# Main.net
KiCad netlist of a schematic drawn in Altium Designer
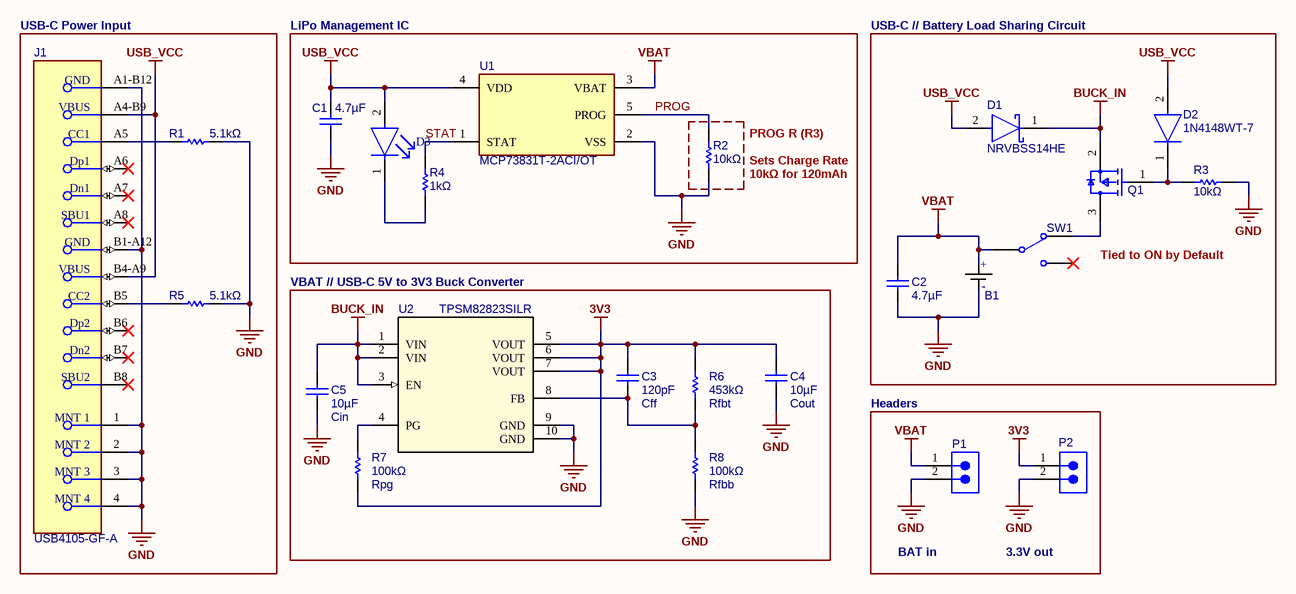
[diagram p0: Main.SchDoc]

(export (version "E")
  (design (tool "Eeschema 10.0.6"))
  (components
    (comp (ref "B1") (value "LiPo") (libsource (lib "LiPoSchematicLibrary") (part "3.7V 30mAh LiPo")))
    (comp (ref "C1")
      (value "4.7µF")
      (footprint "WCAP-CSGP_0603_L1.6W0.8H0.8_Reflow")
      (libsource (lib "Altium Content Vault") (part "Capacitor_Non-Polarized"))
    )
    (comp (ref "C2")
      (value "4.7µF")
      (footprint "WCAP-CSGP_0603_L1.6W0.8H0.8_Reflow")
      (libsource (lib "Altium Content Vault") (part "Capacitor_Non-Polarized"))
    )
    (comp (ref "C3")
      (value "120pF")
      (footprint "WCAP-CSGP_0603_L1.6W0.8H0.8_Reflow")
      (libsource (lib "Altium Content Vault") (part "Capacitor_Non-Polarized"))
    )
    (comp (ref "C4")
      (value "10µF")
      (footprint "WCAP-CSGP_0603_L1.6W0.8H0.8_Reflow")
      (description "10V tolerance")
      (libsource (lib "Altium Content Vault") (part "Capacitor_Non-Polarized"))
    )
    (comp (ref "C5")
      (value "10µF")
      (footprint "WCAP-CSGP_0603_L1.6W0.8H0.8_Reflow")
      (libsource (lib "Altium Content Vault") (part "Capacitor_Non-Polarized"))
    )
    (comp (ref "D1")
      (value "NRVBSS14HE")
      (footprint "FP-477AD-MFG")
      (description "NRVBSS14HE Rectifier Diode, Schottky, 1 Phase, 1 Element, 1A, 40V V(RRM), Silicon")
      (libsource (lib "Altium Content Vault") (part "c1678fac7984e62e0809fbf79c06691"))
    )
    (comp (ref "D2")
      (value "1N4148WT-7")
      (footprint "FP-SOD523-MFG")
      (description "DIODE GEN PURP 80V 125MA SOD523")
      (libsource (lib "Altium Content Vault") (part "d7152d700b627762746794eb795d46e"))
    )
    (comp (ref "D3")
      (value "LTST-C190KGKT")
      (footprint "FP-LTST-C190KGKT-MFG")
      (description "LED GREEN CLEAR CHIP SMD")
      (libsource (lib "Altium Content Vault") (part "8706943c75ba83719d021d2fdc84c58"))
    )
    (comp (ref "J1")
      (value "USB4105-GF-A")
      (footprint "FP-USB4105-GF-A-MFG")
      (description "CONN RCPT USB2.0 TYPEC 5A")
      (fields
        (field (name "MANUFACTURER") "GCT")
        (field (name "OCTOPART") "https://octopart.com/usb4105-gf-a-gct-106627878")
      )
      (libsource (lib "Altium Content Vault") (part "e7c17a616881a82b79941196b4bec10"))
    )
    (comp (ref "P1")
      (value "61300211121")
      (footprint "61300211121")
      (libsource (lib "Altium Content Vault") (part "Header_Male_1R_02P"))
    )
    (comp (ref "P2")
      (value "61300211121")
      (footprint "61300211121")
      (libsource (lib "Altium Content Vault") (part "Header_Male_1R_02P"))
    )
    (comp (ref "Q1")
      (value "IRLML6402TRPBF")
      (footprint "FP-Micro3-MFG")
      (description "MOSFET P-CH 20V 3.7A SOT-23")
      (fields
        (field (name "OCTOPART") "https://octopart.com/irlml6402trpbf-infineon-65874989")
        (field (name "MANUFACTURER") "Infineon")
      )
      (libsource (lib "Altium Content Vault") (part "566027c8dc92b5207d53ac25ab3eb60"))
    )
    (comp (ref "R1")
      (value "5.1kΩ")
      (footprint "RESC1608X55X25NL10T15")
      (libsource (lib "Altium Content Vault") (part "RES"))
    )
    (comp (ref "R2")
      (value "10kΩ")
      (footprint "RESC1608X55X25NL10T15")
      (libsource (lib "Altium Content Vault") (part "RES"))
    )
    (comp (ref "R3")
      (value "10kΩ")
      (footprint "RESC1608X55X25NL10T15")
      (libsource (lib "Altium Content Vault") (part "RES"))
    )
    (comp (ref "R4")
      (value "1kΩ")
      (footprint "RESC1608X55X25NL10T15")
      (libsource (lib "Altium Content Vault") (part "RES"))
    )
    (comp (ref "R5")
      (value "5.1kΩ")
      (footprint "RESC1608X55X25NL10T15")
      (libsource (lib "Altium Content Vault") (part "RES"))
    )
    (comp (ref "R6")
      (value "453kΩ")
      (footprint "RESC1608X55X25NL10T15")
      (libsource (lib "Altium Content Vault") (part "RES"))
    )
    (comp (ref "R7")
      (value "100kΩ")
      (footprint "RESC1608X55X25NL10T15")
      (libsource (lib "Altium Content Vault") (part "RES"))
    )
    (comp (ref "R8")
      (value "100kΩ")
      (footprint "RESC1608X55X25NL10T15")
      (libsource (lib "Altium Content Vault") (part "RES"))
    )
    (comp (ref "SW1")
      (value "450404015514")
      (footprint "450404015514")
      (description "450404015514 Slide Switch, 0.3A, 5Vdc, Smd Rohs Compliant: Yes")
      (libsource (lib "Altium Content Vault") (part "SPDT"))
    )
    (comp (ref "U1")
      (value "MCP73831T-2ACI/OT")
      (footprint "FP-C04-091-OT-IPC_B")
      (description "IC CONTROLLR LI-ION 4.2V SOT23-5")
      (libsource (lib "Altium Content Vault") (part "61f5a3bb3429d9e0caadea342aa3b19"))
    )
    (comp (ref "U2")
      (value "TPSM82823SILR")
      (footprint "SIL0010D-MFG")
      (description "No Description Available")
      (libsource (lib "TPSM82823SILR") (part "TPSM82823SILR"))
    )
  )
  (nets
    (net (code "1") (name "/PROG") (class "Default")
      (node (ref "R2") (pin "1") (pinfunction "1_1") (pintype "passive"))
      (node (ref "U1") (pin "5") (pinfunction "PROG_5") (pintype "passive"))
    )
    (net (code "2") (name "/STAT") (class "Default")
      (node (ref "R4") (pin "2") (pinfunction "2_2") (pintype "passive"))
      (node (ref "U1") (pin "1") (pinfunction "STAT_1") (pintype "passive"))
    )
    (net (code "3") (name "3V3") (class "Default")
      (node (ref "C3") (pin "2") (pinfunction "2_2") (pintype "passive"))
      (node (ref "C4") (pin "2") (pinfunction "2_2") (pintype "passive"))
      (node (ref "P2") (pin "1") (pinfunction "1_1") (pintype "passive"))
      (node (ref "R6") (pin "1") (pinfunction "1_1") (pintype "passive"))
      (node (ref "R7") (pin "2") (pinfunction "2_2") (pintype "passive"))
      (node (ref "U2") (pin "5") (pinfunction "VOUT_5") (pintype "power_in"))
      (node (ref "U2") (pin "6") (pinfunction "VOUT_6") (pintype "power_in"))
      (node (ref "U2") (pin "7") (pinfunction "VOUT_7") (pintype "power_in"))
    )
    (net (code "4") (name "BUCK_IN") (class "Default")
      (node (ref "C5") (pin "2") (pinfunction "2_2") (pintype "passive"))
      (node (ref "D1") (pin "1") (pinfunction "C_1") (pintype "passive"))
      (node (ref "Q1") (pin "2") (pinfunction "S_2") (pintype "passive"))
      (node (ref "U2") (pin "1") (pinfunction "VIN_1") (pintype "power_in"))
      (node (ref "U2") (pin "2") (pinfunction "VIN_2") (pintype "power_in"))
      (node (ref "U2") (pin "3") (pinfunction "EN_3") (pintype "input"))
    )
    (net (code "5") (name "GND") (class "Default")
      (node (ref "B1") (pin "1") (pinfunction "-_1") (pintype "passive"))
      (node (ref "C1") (pin "1") (pinfunction "1_1") (pintype "passive"))
      (node (ref "C2") (pin "1") (pinfunction "1_1") (pintype "passive"))
      (node (ref "C4") (pin "1") (pinfunction "1_1") (pintype "passive"))
      (node (ref "C5") (pin "1") (pinfunction "1_1") (pintype "passive"))
      (node (ref "J1") (pin "1") (pinfunction "MNT_1_1") (pintype "power_in"))
      (node (ref "J1") (pin "2") (pinfunction "MNT_2_2") (pintype "power_in"))
      (node (ref "J1") (pin "3") (pinfunction "MNT_3_3") (pintype "power_in"))
      (node (ref "J1") (pin "4") (pinfunction "MNT_4_4") (pintype "power_in"))
      (node (ref "J1") (pin "A1-B12") (pinfunction "GND_A1-B12") (pintype "power_in"))
      (node (ref "J1") (pin "B1-A12") (pinfunction "GND_B1-A12") (pintype "bidirectional"))
      (node (ref "P1") (pin "2") (pinfunction "2_2") (pintype "passive"))
      (node (ref "P2") (pin "2") (pinfunction "2_2") (pintype "passive"))
      (node (ref "R1") (pin "1") (pinfunction "1_1") (pintype "passive"))
      (node (ref "R2") (pin "2") (pinfunction "2_2") (pintype "passive"))
      (node (ref "R3") (pin "2") (pinfunction "2_2") (pintype "passive"))
      (node (ref "R5") (pin "1") (pinfunction "1_1") (pintype "passive"))
      (node (ref "R8") (pin "2") (pinfunction "2_2") (pintype "passive"))
      (node (ref "U1") (pin "2") (pinfunction "VSS_2") (pintype "power_in"))
      (node (ref "U2") (pin "10") (pinfunction "GND_10") (pintype "power_in"))
      (node (ref "U2") (pin "9") (pinfunction "GND_9") (pintype "power_in"))
    )
    (net (code "6") (name "Net-(D2-C)") (class "Default")
      (node (ref "D2") (pin "1") (pinfunction "C_1") (pintype "passive"))
      (node (ref "Q1") (pin "1") (pinfunction "G_1") (pintype "passive"))
      (node (ref "R3") (pin "1") (pinfunction "1_1") (pintype "passive"))
    )
    (net (code "7") (name "Net-(D3-C)") (class "Default")
      (node (ref "D3") (pin "1") (pinfunction "C_1") (pintype "passive"))
      (node (ref "R4") (pin "1") (pinfunction "1_1") (pintype "passive"))
    )
    (net (code "8") (name "Net-(J1-CC1)") (class "Default")
      (node (ref "J1") (pin "A5") (pinfunction "CC1_A5") (pintype "power_in"))
      (node (ref "R1") (pin "2") (pinfunction "2_2") (pintype "passive"))
    )
    (net (code "9") (name "Net-(J1-CC2)") (class "Default")
      (node (ref "J1") (pin "B5") (pinfunction "CC2_B5") (pintype "bidirectional"))
      (node (ref "R5") (pin "2") (pinfunction "2_2") (pintype "passive"))
    )
    (net (code "10") (name "Net-(Q1-D)") (class "Default")
      (node (ref "Q1") (pin "3") (pinfunction "D_3") (pintype "passive"))
      (node (ref "SW1") (pin "L1") (pinfunction "L1_L1") (pintype "passive"))
    )
    (net (code "11") (name "Net-(U2-FB)") (class "Default")
      (node (ref "C3") (pin "1") (pinfunction "1_1") (pintype "passive"))
      (node (ref "R6") (pin "2") (pinfunction "2_2") (pintype "passive"))
      (node (ref "R8") (pin "1") (pinfunction "1_1") (pintype "passive"))
      (node (ref "U2") (pin "8") (pinfunction "FB_8") (pintype "passive"))
    )
    (net (code "12") (name "Net-(U2-PG)") (class "Default")
      (node (ref "R7") (pin "1") (pinfunction "1_1") (pintype "passive"))
      (node (ref "U2") (pin "4") (pinfunction "PG_4") (pintype "open_collector"))
    )
    (net (code "13") (name "USB_VCC") (class "Default")
      (node (ref "C1") (pin "2") (pinfunction "2_2") (pintype "passive"))
      (node (ref "D1") (pin "2") (pinfunction "A_2") (pintype "passive"))
      (node (ref "D2") (pin "2") (pinfunction "A_2") (pintype "passive"))
      (node (ref "D3") (pin "2") (pinfunction "A_2") (pintype "passive"))
      (node (ref "J1") (pin "A4-B9") (pinfunction "VBUS_A4-B9") (pintype "power_in"))
      (node (ref "J1") (pin "B4-A9") (pinfunction "VBUS_B4-A9") (pintype "bidirectional"))
      (node (ref "U1") (pin "4") (pinfunction "VDD_4") (pintype "power_in"))
    )
    (net (code "14") (name "VBAT") (class "Default")
      (node (ref "B1") (pin "0") (pinfunction "+_0") (pintype "passive"))
      (node (ref "C2") (pin "2") (pinfunction "2_2") (pintype "passive"))
      (node (ref "P1") (pin "1") (pinfunction "1_1") (pintype "passive"))
      (node (ref "SW1") (pin "COM") (pinfunction "COM_COM") (pintype "passive"))
      (node (ref "U1") (pin "3") (pinfunction "VBAT_3") (pintype "power_in"))
    )
    (net (code "15") (name "unconnected-(J1-Dn1-PadA7)") (class "Default")
      (node (ref "J1") (pin "A7") (pinfunction "Dn1_A7") (pintype "bidirectional+no_connect"))
    )
    (net (code "16") (name "unconnected-(J1-Dn2-PadB7)") (class "Default")
      (node (ref "J1") (pin "B7") (pinfunction "Dn2_B7") (pintype "bidirectional+no_connect"))
    )
    (net (code "17") (name "unconnected-(J1-Dp1-PadA6)") (class "Default")
      (node (ref "J1") (pin "A6") (pinfunction "Dp1_A6") (pintype "bidirectional+no_connect"))
    )
    (net (code "18") (name "unconnected-(J1-Dp2-PadB6)") (class "Default")
      (node (ref "J1") (pin "B6") (pinfunction "Dp2_B6") (pintype "bidirectional+no_connect"))
    )
    (net (code "19") (name "unconnected-(J1-SBU1-PadA8)") (class "Default")
      (node (ref "J1") (pin "A8") (pinfunction "SBU1_A8") (pintype "bidirectional+no_connect"))
    )
    (net (code "20") (name "unconnected-(J1-SBU2-PadB8)") (class "Default")
      (node (ref "J1") (pin "B8") (pinfunction "SBU2_B8") (pintype "power_in+no_connect"))
    )
    (net (code "21") (name "unconnected-(SW1-PadL2)") (class "Default")
      (node (ref "SW1") (pin "L2") (pinfunction "L2_L2") (pintype "passive+no_connect"))
    )
  )
)
